# Probe_Switches.net
KiCad netlist of a schematic drawn in Altium Designer
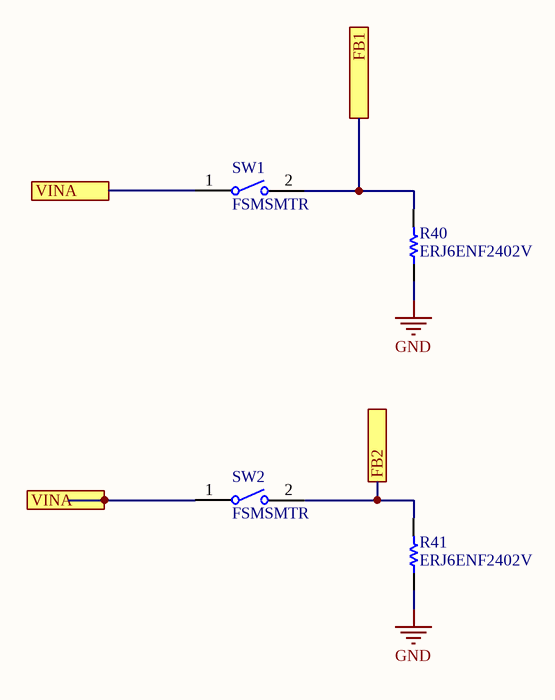
[diagram p0: Probe_Switches.SchDoc]

(export (version "E")
  (design (tool "Eeschema 10.0.6"))
  (components
    (comp (ref "R40")
      (value "ERJ6ENF2402V")
      (footprint "RESC2013X70X40ML20T20")
      (fields (field (name "MANUFACTURER") "Panasonic"))
      (libsource (lib "Altium Content Vault") (part "RES"))
    )
    (comp (ref "R41")
      (value "ERJ6ENF2402V")
      (footprint "RESC2013X70X40ML20T20")
      (fields (field (name "MANUFACTURER") "Panasonic"))
      (libsource (lib "Altium Content Vault") (part "RES"))
    )
    (comp (ref "SW1")
      (value "FSMSMTR")
      (footprint "TECO-FSMSMTR_V")
      (description "FSMSM Push Button Switch, 50 mA, -35 to 85 degC, 2-Pin SMD, RoHS, Tape and Reel")
      (fields (field (name "MANUFACTURER") "TE Connectivity"))
      (libsource (lib "Altium Content Vault") (part "SW-SPST-2_C"))
    )
    (comp (ref "SW2")
      (value "FSMSMTR")
      (footprint "TECO-FSMSMTR_V")
      (description "FSMSM Push Button Switch, 50 mA, -35 to 85 degC, 2-Pin SMD, RoHS, Tape and Reel")
      (fields (field (name "MANUFACTURER") "TE Connectivity"))
      (libsource (lib "Altium Content Vault") (part "SW-SPST-2_C"))
    )
  )
  (nets
    (net (code "1") (name "/FB1") (class "Default")
      (node (ref "R40") (pin "2") (pinfunction "2_2") (pintype "passive"))
      (node (ref "SW1") (pin "2") (pinfunction "2_2") (pintype "passive"))
    )
    (net (code "2") (name "/FB2") (class "Default")
      (node (ref "R41") (pin "2") (pinfunction "2_2") (pintype "passive"))
      (node (ref "SW2") (pin "2") (pinfunction "2_2") (pintype "passive"))
    )
    (net (code "3") (name "/VINA") (class "Default")
      (node (ref "SW1") (pin "1") (pinfunction "1_1") (pintype "passive"))
      (node (ref "SW2") (pin "1") (pinfunction "1_1") (pintype "passive"))
    )
    (net (code "4") (name "GND") (class "Default")
      (node (ref "R40") (pin "1") (pinfunction "1_1") (pintype "passive"))
      (node (ref "R41") (pin "1") (pinfunction "1_1") (pintype "passive"))
    )
  )
)
